# FR_Schematic.net
KiCad netlist of a schematic drawn in EAGLE
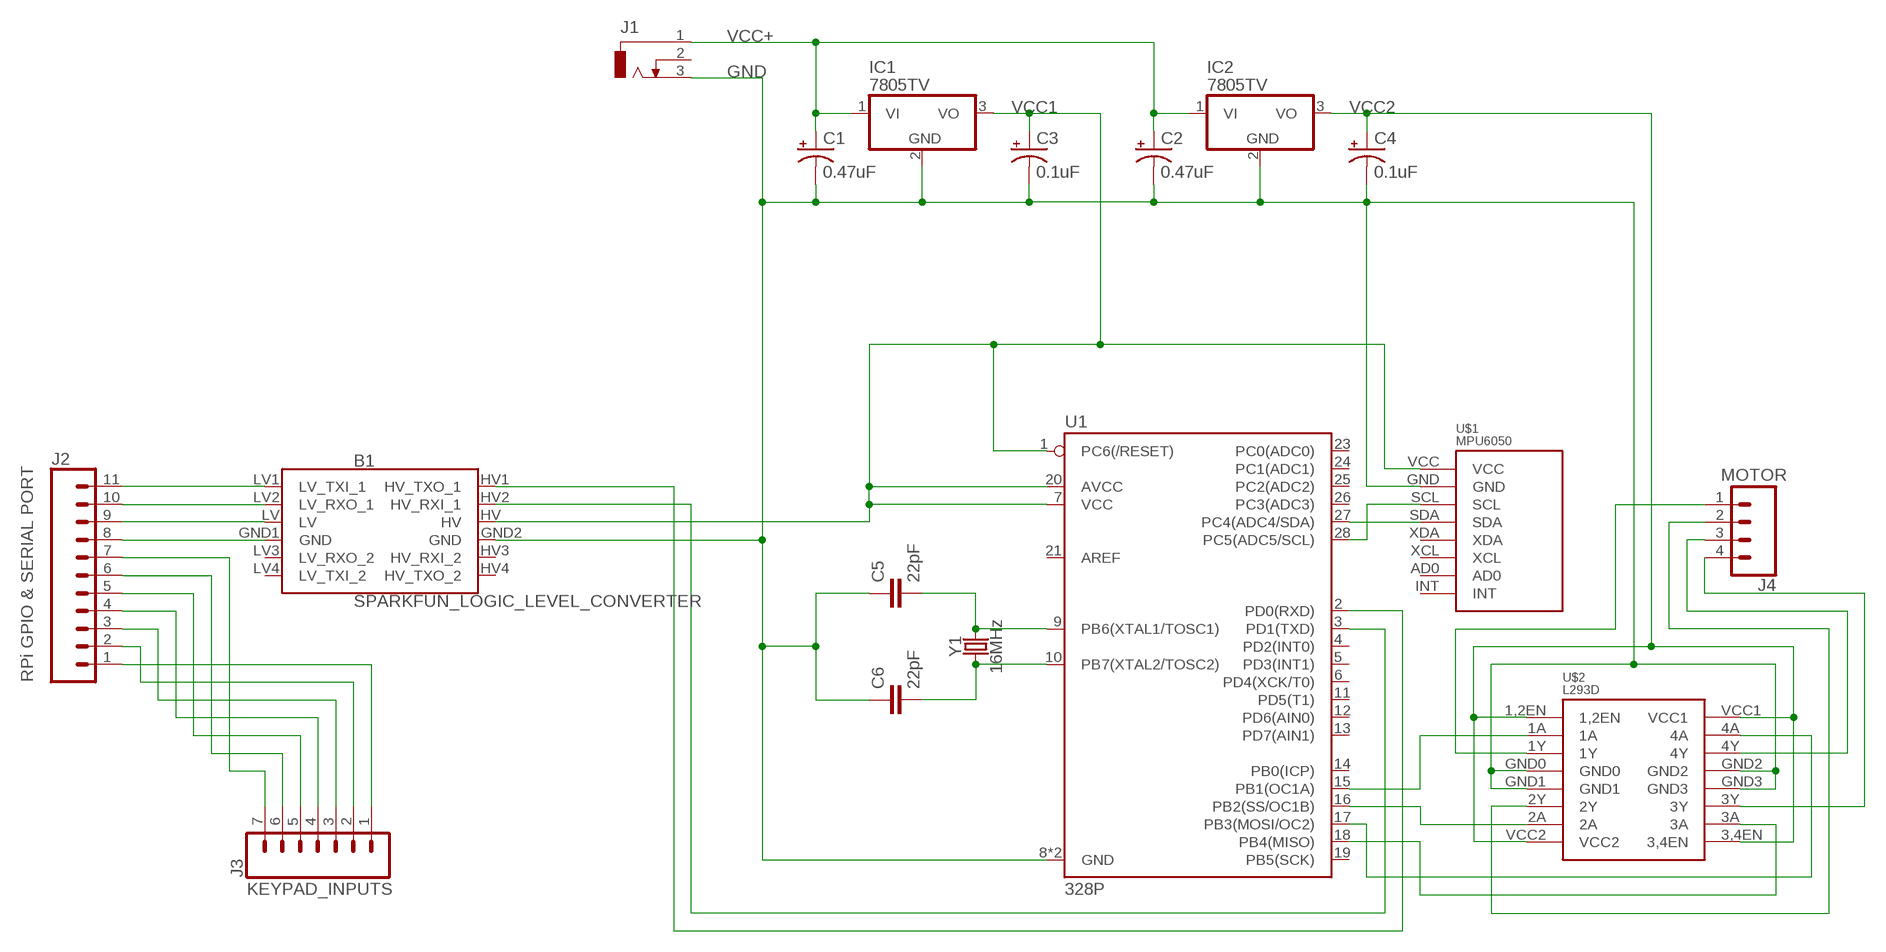
[diagram p0: schematic, sheet 1]

(export (version "E")
  (design (tool "Eeschema 10.0.6"))
  (components
    (comp (ref "B1")
      (value "SPARKFUN_LOGIC_LEVEL_CONVERTER")
      (footprint "eagle-import:SPARKFUN_LOGIC_LEVEL_CONVERTER")
      (libsource (lib "eagle-import") (part "SPARKFUN_LOGIC_LEVEL_CONVERTER"))
    )
    (comp (ref "C1")
      (value "0.47uF")
      (footprint "eagle-import:CPOL-RADIAL-2.5MM-5MM")
      (libsource (lib "eagle-import") (part "10UF-POLAR-RADIAL-2.5MM-25V-20%"))
    )
    (comp (ref "C2")
      (value "0.47uF")
      (footprint "eagle-import:CPOL-RADIAL-2.5MM-5MM")
      (libsource (lib "eagle-import") (part "10UF-POLAR-RADIAL-2.5MM-25V-20%"))
    )
    (comp (ref "C3")
      (value "0.1uF")
      (footprint "eagle-import:E1,8-4")
      (libsource (lib "eagle-import") (part "CPOL-USE1.8-4"))
    )
    (comp (ref "C4")
      (value "0.1uF")
      (footprint "eagle-import:E1,8-4")
      (libsource (lib "eagle-import") (part "CPOL-USE1.8-4"))
    )
    (comp (ref "C5")
      (value "22pF")
      (footprint "eagle-import:CAP-PTH-2.54")
      (libsource (lib "eagle-import") (part "22PF-PTH-2.54MM-200V-5%"))
    )
    (comp (ref "C6")
      (value "22pF")
      (footprint "eagle-import:CAP-PTH-2.54")
      (libsource (lib "eagle-import") (part "22PF-PTH-2.54MM-200V-5%"))
    )
    (comp (ref "IC1")
      (value "7805TV")
      (footprint "eagle-import:TO220V")
      (libsource (lib "eagle-import") (part "78TV05"))
    )
    (comp (ref "IC2")
      (value "7805TV")
      (footprint "eagle-import:TO220V")
      (libsource (lib "eagle-import") (part "78TV05"))
    )
    (comp (ref "J1")
      (value "DCJ0303")
      (footprint "eagle-import:DCJ0303")
      (libsource (lib "eagle-import") (part "DCJ0303"))
    )
    (comp (ref "J2")
      (value "CONN_11")
      (footprint "eagle-import:1X11")
      (libsource (lib "eagle-import") (part "CONN_11"))
    )
    (comp (ref "J3")
      (value "CONN_07")
      (footprint "eagle-import:1X07")
      (libsource (lib "eagle-import") (part "CONN_07"))
    )
    (comp (ref "J4")
      (value "CONN_04PTH")
      (footprint "eagle-import:1X04")
      (libsource (lib "eagle-import") (part "CONN_04PTH"))
    )
    (comp (ref "U$1")
      (value "MPU6050")
      (footprint "eagle-import:MPU6050")
      (libsource (lib "eagle-import") (part "MPU6050"))
    )
    (comp (ref "U$2")
      (value "L293D")
      (footprint "eagle-import:L293D")
      (libsource (lib "eagle-import") (part "L293D"))
    )
    (comp (ref "U1")
      (value "328P")
      (footprint "eagle-import:DIP28")
      (libsource (lib "eagle-import") (part "ATMEGA328P_PDIP"))
    )
    (comp (ref "Y1")
      (value "16MHz")
      (footprint "eagle-import:HC49US")
      (libsource (lib "eagle-import") (part "CRYSTAL-16MHZPTH-HC49US"))
    )
  )
  (nets
    (net (code "1") (name "/GND") (class "Default")
      (node (ref "B1") (pin "GND2") (pinfunction "GND_GND2") (pintype "power_in"))
      (node (ref "C1") (pin "2") (pinfunction "-_2") (pintype "passive"))
      (node (ref "C2") (pin "2") (pinfunction "-_2") (pintype "passive"))
      (node (ref "C3") (pin "-") (pinfunction "-_-") (pintype "passive"))
      (node (ref "C4") (pin "-") (pinfunction "-_-") (pintype "passive"))
      (node (ref "C5") (pin "1") (pinfunction "1_1") (pintype "passive"))
      (node (ref "C6") (pin "1") (pinfunction "1_1") (pintype "passive"))
      (node (ref "IC1") (pin "2") (pinfunction "GND_2") (pintype "passive"))
      (node (ref "IC2") (pin "2") (pinfunction "GND_2") (pintype "passive"))
      (node (ref "J1") (pin "3") (pinfunction "3_3") (pintype "passive"))
      (node (ref "U$1") (pin "GND") (pinfunction "GND_GND") (pintype "bidirectional"))
      (node (ref "U$2") (pin "GND0") (pinfunction "GND0_GND0") (pintype "bidirectional"))
      (node (ref "U$2") (pin "GND1") (pinfunction "GND1_GND1") (pintype "bidirectional"))
      (node (ref "U$2") (pin "GND2") (pinfunction "GND2_GND2") (pintype "bidirectional"))
      (node (ref "U$2") (pin "GND3") (pinfunction "GND3_GND3") (pintype "bidirectional"))
      (node (ref "U1") (pin "22") (pinfunction "GND_22") (pintype "bidirectional"))
      (node (ref "U1") (pin "8") (pinfunction "GND_8") (pintype "bidirectional"))
    )
    (net (code "2") (name "/VCC+") (class "Default")
      (node (ref "C1") (pin "1") (pinfunction "+_1") (pintype "passive"))
      (node (ref "C2") (pin "1") (pinfunction "+_1") (pintype "passive"))
      (node (ref "IC1") (pin "1") (pinfunction "VI_1") (pintype "input"))
      (node (ref "IC2") (pin "1") (pinfunction "VI_1") (pintype "input"))
      (node (ref "J1") (pin "1") (pinfunction "1_1") (pintype "passive"))
    )
    (net (code "3") (name "/VCC1") (class "Default")
      (node (ref "B1") (pin "HV") (pinfunction "HV_HV") (pintype "power_in"))
      (node (ref "C3") (pin "+") (pinfunction "+_+") (pintype "passive"))
      (node (ref "IC1") (pin "3") (pinfunction "VO_3") (pintype "passive"))
      (node (ref "U$1") (pin "VCC") (pinfunction "VCC_VCC") (pintype "bidirectional"))
      (node (ref "U1") (pin "1") (pinfunction "PC6(/RESET)_1") (pintype "bidirectional"))
      (node (ref "U1") (pin "20") (pinfunction "AVCC_20") (pintype "bidirectional"))
      (node (ref "U1") (pin "7") (pinfunction "VCC_7") (pintype "bidirectional"))
    )
    (net (code "4") (name "/VCC2") (class "Default")
      (node (ref "C4") (pin "+") (pinfunction "+_+") (pintype "passive"))
      (node (ref "IC2") (pin "3") (pinfunction "VO_3") (pintype "passive"))
      (node (ref "U$2") (pin "1,2EN") (pinfunction "1,2EN_1,2EN") (pintype "bidirectional"))
      (node (ref "U$2") (pin "3,4EN") (pinfunction "3,4EN_3,4EN") (pintype "bidirectional"))
      (node (ref "U$2") (pin "VCC1") (pinfunction "VCC1_VCC1") (pintype "bidirectional"))
      (node (ref "U$2") (pin "VCC2") (pinfunction "VCC2_VCC2") (pintype "bidirectional"))
    )
    (net (code "5") (name "Net-(B1-GND-PadGND1)") (class "Default")
      (node (ref "B1") (pin "GND1") (pinfunction "GND_GND1") (pintype "power_in"))
      (node (ref "J2") (pin "8") (pinfunction "8_8") (pintype "passive"))
    )
    (net (code "6") (name "Net-(B1-HV_RXI_1)") (class "Default")
      (node (ref "B1") (pin "HV2") (pinfunction "HV_RXI_1_HV2") (pintype "bidirectional"))
      (node (ref "U1") (pin "3") (pinfunction "PD1(TXD)_3") (pintype "bidirectional"))
    )
    (net (code "7") (name "Net-(B1-HV_TXO_1)") (class "Default")
      (node (ref "B1") (pin "HV1") (pinfunction "HV_TXO_1_HV1") (pintype "bidirectional"))
      (node (ref "U1") (pin "2") (pinfunction "PD0(RXD)_2") (pintype "bidirectional"))
    )
    (net (code "8") (name "Net-(B1-LV_RXO_1)") (class "Default")
      (node (ref "B1") (pin "LV2") (pinfunction "LV_RXO_1_LV2") (pintype "bidirectional"))
      (node (ref "J2") (pin "10") (pinfunction "10_10") (pintype "passive"))
    )
    (net (code "9") (name "Net-(B1-LV_TXI_1)") (class "Default")
      (node (ref "B1") (pin "LV1") (pinfunction "LV_TXI_1_LV1") (pintype "bidirectional"))
      (node (ref "J2") (pin "11") (pinfunction "11_11") (pintype "passive"))
    )
    (net (code "10") (name "Net-(B1-PadLV)") (class "Default")
      (node (ref "B1") (pin "LV") (pinfunction "LV_LV") (pintype "power_in"))
      (node (ref "J2") (pin "9") (pinfunction "9_9") (pintype "passive"))
    )
    (net (code "11") (name "Net-(J2-Pad1)") (class "Default")
      (node (ref "J2") (pin "1") (pinfunction "1_1") (pintype "passive"))
      (node (ref "J3") (pin "1") (pinfunction "1_1") (pintype "passive"))
    )
    (net (code "12") (name "Net-(J2-Pad2)") (class "Default")
      (node (ref "J2") (pin "2") (pinfunction "2_2") (pintype "passive"))
      (node (ref "J3") (pin "2") (pinfunction "2_2") (pintype "passive"))
    )
    (net (code "13") (name "Net-(J2-Pad3)") (class "Default")
      (node (ref "J2") (pin "3") (pinfunction "3_3") (pintype "passive"))
      (node (ref "J3") (pin "3") (pinfunction "3_3") (pintype "passive"))
    )
    (net (code "14") (name "Net-(J2-Pad4)") (class "Default")
      (node (ref "J2") (pin "4") (pinfunction "4_4") (pintype "passive"))
      (node (ref "J3") (pin "4") (pinfunction "4_4") (pintype "passive"))
    )
    (net (code "15") (name "Net-(J2-Pad5)") (class "Default")
      (node (ref "J2") (pin "5") (pinfunction "5_5") (pintype "passive"))
      (node (ref "J3") (pin "5") (pinfunction "5_5") (pintype "passive"))
    )
    (net (code "16") (name "Net-(J2-Pad6)") (class "Default")
      (node (ref "J2") (pin "6") (pinfunction "6_6") (pintype "passive"))
      (node (ref "J3") (pin "6") (pinfunction "6_6") (pintype "passive"))
    )
    (net (code "17") (name "Net-(J2-Pad7)") (class "Default")
      (node (ref "J2") (pin "7") (pinfunction "7_7") (pintype "passive"))
      (node (ref "J3") (pin "7") (pinfunction "7_7") (pintype "passive"))
    )
    (net (code "18") (name "Net-(J4-Pad1)") (class "Default")
      (node (ref "J4") (pin "1") (pinfunction "1_1") (pintype "passive"))
      (node (ref "U$2") (pin "1Y") (pinfunction "1Y_1Y") (pintype "bidirectional"))
    )
    (net (code "19") (name "Net-(J4-Pad2)") (class "Default")
      (node (ref "J4") (pin "2") (pinfunction "2_2") (pintype "passive"))
      (node (ref "U$2") (pin "2Y") (pinfunction "2Y_2Y") (pintype "bidirectional"))
    )
    (net (code "20") (name "Net-(J4-Pad3)") (class "Default")
      (node (ref "J4") (pin "3") (pinfunction "3_3") (pintype "passive"))
      (node (ref "U$2") (pin "4Y") (pinfunction "4Y_4Y") (pintype "bidirectional"))
    )
    (net (code "21") (name "Net-(J4-Pad4)") (class "Default")
      (node (ref "J4") (pin "4") (pinfunction "4_4") (pintype "passive"))
      (node (ref "U$2") (pin "3Y") (pinfunction "3Y_3Y") (pintype "bidirectional"))
    )
    (net (code "22") (name "Net-(U1-PB1(OC1A))") (class "Default")
      (node (ref "U$2") (pin "1A") (pinfunction "1A_1A") (pintype "bidirectional"))
      (node (ref "U1") (pin "15") (pinfunction "PB1(OC1A)_15") (pintype "bidirectional"))
    )
    (net (code "23") (name "Net-(U1-PB2(SS{slash}OC1B))") (class "Default")
      (node (ref "U$2") (pin "2A") (pinfunction "2A_2A") (pintype "bidirectional"))
      (node (ref "U1") (pin "16") (pinfunction "PB2(SS/OC1B)_16") (pintype "bidirectional"))
    )
    (net (code "24") (name "Net-(U1-PB3(MOSI{slash}OC2))") (class "Default")
      (node (ref "U$2") (pin "4A") (pinfunction "4A_4A") (pintype "bidirectional"))
      (node (ref "U1") (pin "17") (pinfunction "PB3(MOSI/OC2)_17") (pintype "bidirectional"))
    )
    (net (code "25") (name "Net-(U1-PB4(MISO))") (class "Default")
      (node (ref "U$2") (pin "3A") (pinfunction "3A_3A") (pintype "bidirectional"))
      (node (ref "U1") (pin "18") (pinfunction "PB4(MISO)_18") (pintype "bidirectional"))
    )
    (net (code "26") (name "Net-(U1-PB6(XTAL1{slash}TOSC1))") (class "Default")
      (node (ref "C5") (pin "2") (pinfunction "2_2") (pintype "passive"))
      (node (ref "U1") (pin "9") (pinfunction "PB6(XTAL1/TOSC1)_9") (pintype "bidirectional"))
      (node (ref "Y1") (pin "2") (pinfunction "2_2") (pintype "passive"))
    )
    (net (code "27") (name "Net-(U1-PB7(XTAL2{slash}TOSC2))") (class "Default")
      (node (ref "C6") (pin "2") (pinfunction "2_2") (pintype "passive"))
      (node (ref "U1") (pin "10") (pinfunction "PB7(XTAL2/TOSC2)_10") (pintype "bidirectional"))
      (node (ref "Y1") (pin "1") (pinfunction "1_1") (pintype "passive"))
    )
    (net (code "28") (name "Net-(U1-PC4(ADC4{slash}SDA))") (class "Default")
      (node (ref "U$1") (pin "SDA") (pinfunction "SDA_SDA") (pintype "bidirectional"))
      (node (ref "U1") (pin "27") (pinfunction "PC4(ADC4/SDA)_27") (pintype "bidirectional"))
    )
    (net (code "29") (name "Net-(U1-PC5(ADC5{slash}SCL))") (class "Default")
      (node (ref "U$1") (pin "SCL") (pinfunction "SCL_SCL") (pintype "bidirectional"))
      (node (ref "U1") (pin "28") (pinfunction "PC5(ADC5/SCL)_28") (pintype "bidirectional"))
    )
    (net (code "30") (name "unconnected-(B1-HV_RXI_2-PadHV3)") (class "Default")
      (node (ref "B1") (pin "HV3") (pinfunction "HV_RXI_2_HV3") (pintype "bidirectional"))
    )
    (net (code "31") (name "unconnected-(B1-HV_TXO_2-PadHV4)") (class "Default")
      (node (ref "B1") (pin "HV4") (pinfunction "HV_TXO_2_HV4") (pintype "bidirectional"))
    )
    (net (code "32") (name "unconnected-(B1-LV_RXO_2-PadLV3)") (class "Default")
      (node (ref "B1") (pin "LV3") (pinfunction "LV_RXO_2_LV3") (pintype "bidirectional"))
    )
    (net (code "33") (name "unconnected-(B1-LV_TXI_2-PadLV4)") (class "Default")
      (node (ref "B1") (pin "LV4") (pinfunction "LV_TXI_2_LV4") (pintype "bidirectional"))
    )
    (net (code "34") (name "unconnected-(J1-Pad2)") (class "Default")
      (node (ref "J1") (pin "2") (pinfunction "2_2") (pintype "passive"))
    )
    (net (code "35") (name "unconnected-(U$1-PadAD0)") (class "Default")
      (node (ref "U$1") (pin "AD0") (pinfunction "AD0_AD0") (pintype "bidirectional"))
    )
    (net (code "36") (name "unconnected-(U$1-PadINT)") (class "Default")
      (node (ref "U$1") (pin "INT") (pinfunction "INT_INT") (pintype "bidirectional"))
    )
    (net (code "37") (name "unconnected-(U$1-PadXCL)") (class "Default")
      (node (ref "U$1") (pin "XCL") (pinfunction "XCL_XCL") (pintype "bidirectional"))
    )
    (net (code "38") (name "unconnected-(U$1-PadXDA)") (class "Default")
      (node (ref "U$1") (pin "XDA") (pinfunction "XDA_XDA") (pintype "bidirectional"))
    )
    (net (code "39") (name "unconnected-(U1-AREF-Pad21)") (class "Default")
      (node (ref "U1") (pin "21") (pinfunction "AREF_21") (pintype "bidirectional"))
    )
    (net (code "40") (name "unconnected-(U1-PB0(ICP)-Pad14)") (class "Default")
      (node (ref "U1") (pin "14") (pinfunction "PB0(ICP)_14") (pintype "bidirectional"))
    )
    (net (code "41") (name "unconnected-(U1-PB5(SCK)-Pad19)") (class "Default")
      (node (ref "U1") (pin "19") (pinfunction "PB5(SCK)_19") (pintype "bidirectional"))
    )
    (net (code "42") (name "unconnected-(U1-PC0(ADC0)-Pad23)") (class "Default")
      (node (ref "U1") (pin "23") (pinfunction "PC0(ADC0)_23") (pintype "bidirectional"))
    )
    (net (code "43") (name "unconnected-(U1-PC1(ADC1)-Pad24)") (class "Default")
      (node (ref "U1") (pin "24") (pinfunction "PC1(ADC1)_24") (pintype "bidirectional"))
    )
    (net (code "44") (name "unconnected-(U1-PC2(ADC2)-Pad25)") (class "Default")
      (node (ref "U1") (pin "25") (pinfunction "PC2(ADC2)_25") (pintype "bidirectional"))
    )
    (net (code "45") (name "unconnected-(U1-PC3(ADC3)-Pad26)") (class "Default")
      (node (ref "U1") (pin "26") (pinfunction "PC3(ADC3)_26") (pintype "bidirectional"))
    )
    (net (code "46") (name "unconnected-(U1-PD2(INT0)-Pad4)") (class "Default")
      (node (ref "U1") (pin "4") (pinfunction "PD2(INT0)_4") (pintype "bidirectional"))
    )
    (net (code "47") (name "unconnected-(U1-PD3(INT1)-Pad5)") (class "Default")
      (node (ref "U1") (pin "5") (pinfunction "PD3(INT1)_5") (pintype "bidirectional"))
    )
    (net (code "48") (name "unconnected-(U1-PD4(XCK{slash}T0)-Pad6)") (class "Default")
      (node (ref "U1") (pin "6") (pinfunction "PD4(XCK/T0)_6") (pintype "bidirectional"))
    )
    (net (code "49") (name "unconnected-(U1-PD5(T1)-Pad11)") (class "Default")
      (node (ref "U1") (pin "11") (pinfunction "PD5(T1)_11") (pintype "bidirectional"))
    )
    (net (code "50") (name "unconnected-(U1-PD6(AIN0)-Pad12)") (class "Default")
      (node (ref "U1") (pin "12") (pinfunction "PD6(AIN0)_12") (pintype "bidirectional"))
    )
    (net (code "51") (name "unconnected-(U1-PD7(AIN1)-Pad13)") (class "Default")
      (node (ref "U1") (pin "13") (pinfunction "PD7(AIN1)_13") (pintype "bidirectional"))
    )
  )
)
